# BuckBoost.net
KiCad netlist of a schematic drawn in Altium Designer
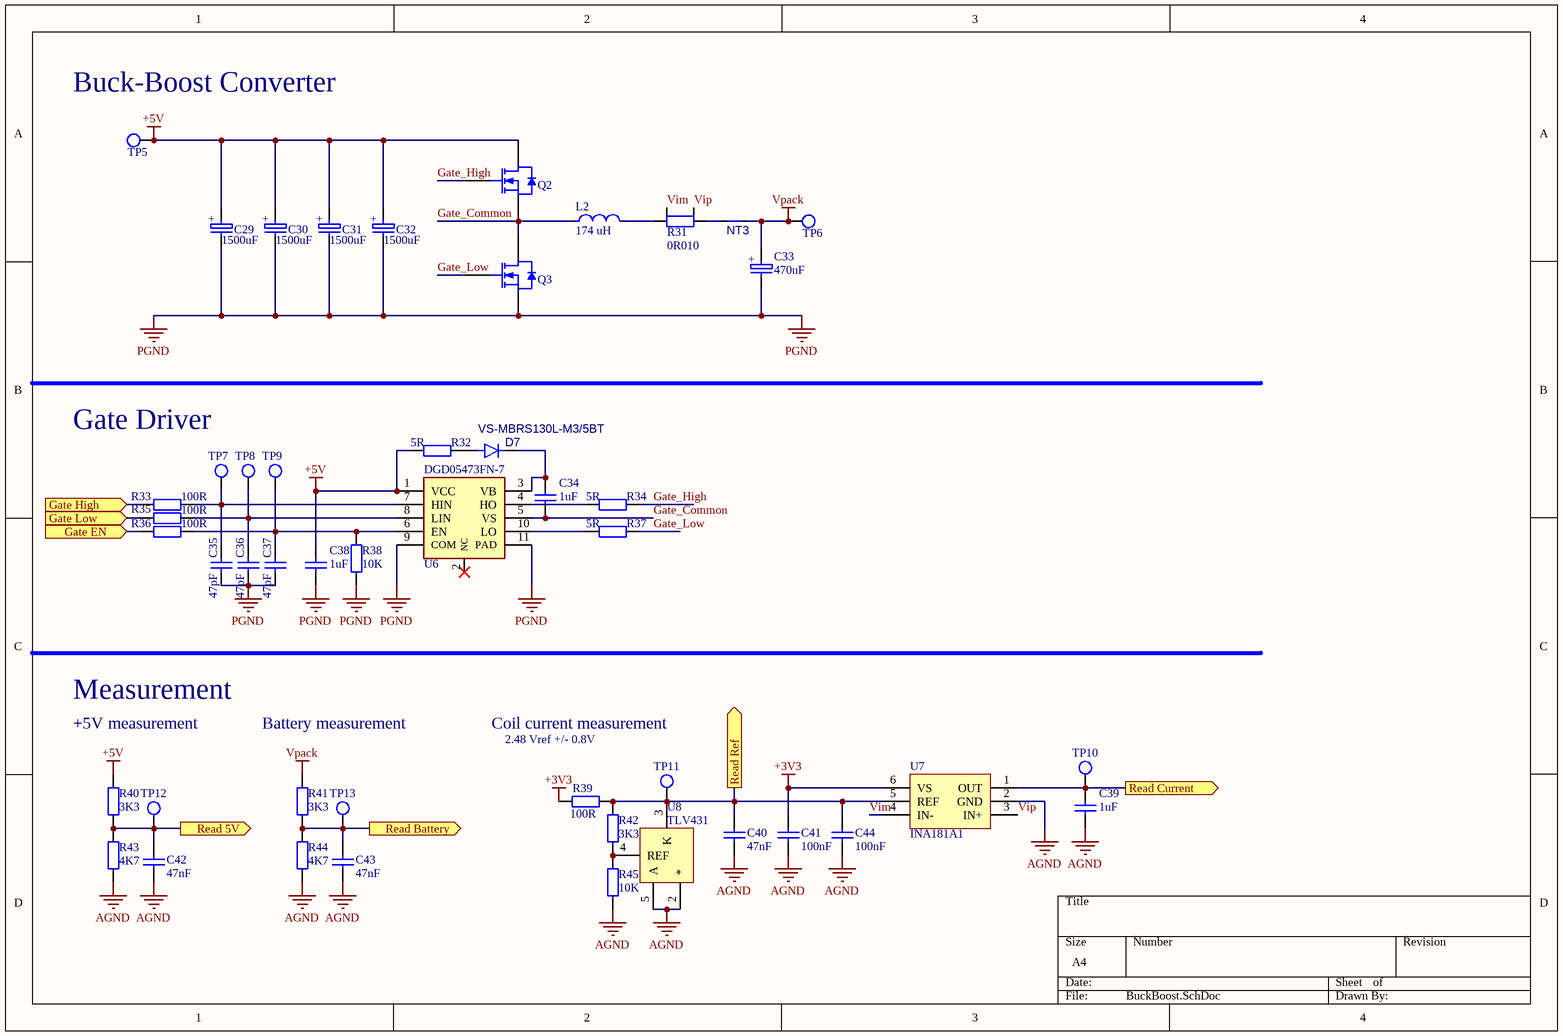
[diagram p0: BuckBoost.SchDoc]

(export (version "E")
  (design (tool "Eeschema 10.0.6"))
  (components
    (comp (ref "C29")
      (value "1500uF")
      (footprint "Aluminium Capacitor 10x12.5")
      (fields
        (field (name "MANUFACTURER") "Nichicon")
        (field (name "MANUFACTURER PART NUMBER") "RNU0J152MDN1PH")
      )
      (libsource (lib "UPS_Schlib") (part "RNU0J152MDN1PH"))
    )
    (comp (ref "C30")
      (value "1500uF")
      (footprint "Aluminium Capacitor 10x12.5")
      (fields
        (field (name "MANUFACTURER") "Nichicon")
        (field (name "MANUFACTURER PART NUMBER") "RNU0J152MDN1PH")
      )
      (libsource (lib "UPS_Schlib") (part "RNU0J152MDN1PH"))
    )
    (comp (ref "C31")
      (value "1500uF")
      (footprint "Aluminium Capacitor 10x12.5")
      (fields
        (field (name "MANUFACTURER") "Nichicon")
        (field (name "MANUFACTURER PART NUMBER") "RNU0J152MDN1PH")
      )
      (libsource (lib "UPS_Schlib") (part "RNU0J152MDN1PH"))
    )
    (comp (ref "C32")
      (value "1500uF")
      (footprint "Aluminium Capacitor 10x12.5")
      (fields
        (field (name "MANUFACTURER") "Nichicon")
        (field (name "MANUFACTURER PART NUMBER") "RNU0J152MDN1PH")
      )
      (libsource (lib "UPS_Schlib") (part "RNU0J152MDN1PH"))
    )
    (comp (ref "C33")
      (value "470uF")
      (footprint "Aluminium Capacitor 10x12.5")
      (description "Aluminum Electrolytic Capacitor, Aluminum (solid Polymer)")
      (fields
        (field (name "MANUFACTURER") "Nichicon")
        (field (name "MANUFACTURER PART NUMBER") "RR50J471MDN1KX")
      )
      (libsource (lib "UPS_Schlib") (part "RR50J471MDN1KX"))
    )
    (comp (ref "C34")
      (value "1uF")
      (footprint "CAP0603")
      (description "Capacitor")
      (libsource (lib "UPS_Schlib") (part "1uF"))
    )
    (comp (ref "C35")
      (value "47pF")
      (footprint "CAP0603")
      (fields
        (field (name "MANUFACTURER") "KEMET")
        (field (name "MANUFACTURER PART NUMBER") "C0603C470J1GACTU")
      )
      (libsource (lib "UPS_Schlib") (part "47pF"))
    )
    (comp (ref "C36")
      (value "47pF")
      (footprint "CAP0603")
      (fields
        (field (name "MANUFACTURER") "KEMET")
        (field (name "MANUFACTURER PART NUMBER") "C0603C470J1GACTU")
      )
      (libsource (lib "UPS_Schlib") (part "47pF"))
    )
    (comp (ref "C37")
      (value "47pF")
      (footprint "CAP0603")
      (fields
        (field (name "MANUFACTURER") "KEMET")
        (field (name "MANUFACTURER PART NUMBER") "C0603C470J1GACTU")
      )
      (libsource (lib "UPS_Schlib") (part "47pF"))
    )
    (comp (ref "C38")
      (value "1uF")
      (footprint "CAP0603")
      (description "Capacitor")
      (libsource (lib "UPS_Schlib") (part "1uF"))
    )
    (comp (ref "C39")
      (value "1uF")
      (footprint "CAP0603")
      (description "Capacitor")
      (libsource (lib "UPS_Schlib") (part "1uF"))
    )
    (comp (ref "C40")
      (value "47nF")
      (footprint "CAP0603")
      (description "Capacitor")
      (libsource (lib "UPS_Schlib") (part "47nF"))
    )
    (comp (ref "C41")
      (value "100nF")
      (footprint "CAP0603")
      (description "Capacitor")
      (libsource (lib "UPS_Schlib") (part "100nF"))
    )
    (comp (ref "C42")
      (value "47nF")
      (footprint "CAP0603")
      (description "Capacitor")
      (libsource (lib "UPS_Schlib") (part "47nF"))
    )
    (comp (ref "C43")
      (value "47nF")
      (footprint "CAP0603")
      (description "Capacitor")
      (libsource (lib "UPS_Schlib") (part "47nF"))
    )
    (comp (ref "C44")
      (value "100nF")
      (footprint "CAP0603")
      (description "Capacitor")
      (libsource (lib "UPS_Schlib") (part "100nF"))
    )
    (comp (ref "D7")
      (value "VS-MBRS130L-M3/5BT")
      (footprint "SMB")
      (description "Rectifier Diode, Schottky, 1 Phase, 1 Element, 30V V(RRM), Silicon")
      (fields (field (name "MANUFACTURER") "Vishay Semiconductors"))
      (libsource (lib "UPS_Schlib") (part "VS-MBRS130L-M3/5BT"))
    )
    (comp (ref "L2")
      (value "174 uH")
      (footprint "COIL_HANDMADE")
      (description "Hand made inductance")
      (fields (field (name "Comment") "Inductor"))
      (libsource (lib "UPS_Schlib") (part "Inductor"))
    )
    (comp (ref "NT3")
      (value "NetTie_1-1")
      (footprint "NETTIE_1.85MM")
      (description "NetTie 1 -> 1")
      (libsource (lib "UPS_Schlib") (part "NetTie_1-1"))
    )
    (comp (ref "Q2")
      (value "N-MOSFET")
      (footprint "SOT-669-5")
      (fields
        (field (name "MANUFACTURER") "Nexperia")
        (field (name "MANUFACTURER PART NUMBER") "PSMN1R2-25YLDX")
      )
      (libsource (lib "UPS_Schlib") (part "PSMN1R2-25YLDX"))
    )
    (comp (ref "Q3")
      (value "N-MOSFET")
      (footprint "SOT-669-5")
      (fields
        (field (name "MANUFACTURER") "Nexperia")
        (field (name "MANUFACTURER PART NUMBER") "PSMN1R2-25YLDX")
      )
      (libsource (lib "UPS_Schlib") (part "PSMN1R2-25YLDX"))
    )
    (comp (ref "R31")
      (value "0R010")
      (footprint "RES1206_KELVIN")
      (description "Resistor Current Sense Metal Foil 1206 10m Ohm 1% 1W ±50ppm/°C T/R")
      (fields
        (field (name "MANUFACTURER") "Eaton")
        (field (name "MANUFACTURER PART NUMBER") "MFSA1206R0050FCM")
      )
      (libsource (lib "UPS_Schlib") (part "0R010"))
    )
    (comp (ref "R32")
      (value "5R")
      (footprint "RES0603")
      (description "Resistor")
      (libsource (lib "UPS_Schlib") (part "5R"))
    )
    (comp (ref "R33")
      (value "100R")
      (footprint "RES0603")
      (description "Resistor")
      (libsource (lib "UPS_Schlib") (part "100R"))
    )
    (comp (ref "R34")
      (value "5R")
      (footprint "RES0603")
      (description "Resistor")
      (libsource (lib "UPS_Schlib") (part "5R"))
    )
    (comp (ref "R35")
      (value "100R")
      (footprint "RES0603")
      (description "Resistor")
      (libsource (lib "UPS_Schlib") (part "100R"))
    )
    (comp (ref "R36")
      (value "100R")
      (footprint "RES0603")
      (description "Resistor")
      (libsource (lib "UPS_Schlib") (part "100R"))
    )
    (comp (ref "R37")
      (value "5R")
      (footprint "RES0603")
      (description "Resistor")
      (libsource (lib "UPS_Schlib") (part "5R"))
    )
    (comp (ref "R38")
      (value "10K")
      (footprint "RES0603")
      (description "Resistor")
      (libsource (lib "UPS_Schlib") (part "10K"))
    )
    (comp (ref "R39")
      (value "100R")
      (footprint "RES0603")
      (description "Resistor")
      (libsource (lib "UPS_Schlib") (part "100R"))
    )
    (comp (ref "R40")
      (value "3K3")
      (footprint "RES0603")
      (fields
        (field (name "MANUFACTURER") "Yageo")
        (field (name "MANUFACTURER PART NUMBER") "RC0603FR-073K3P")
      )
      (libsource (lib "UPS_Schlib") (part "3K3"))
    )
    (comp (ref "R41")
      (value "3K3")
      (footprint "RES0603")
      (fields
        (field (name "MANUFACTURER") "Yageo")
        (field (name "MANUFACTURER PART NUMBER") "RC0603FR-073K3P")
      )
      (libsource (lib "UPS_Schlib") (part "3K3"))
    )
    (comp (ref "R42")
      (value "3K3")
      (footprint "RES0603")
      (fields
        (field (name "MANUFACTURER") "Yageo")
        (field (name "MANUFACTURER PART NUMBER") "RC0603FR-073K3P")
      )
      (libsource (lib "UPS_Schlib") (part "3K3"))
    )
    (comp (ref "R43")
      (value "4K7")
      (footprint "RES0603")
      (description "Resistor")
      (libsource (lib "UPS_Schlib") (part "4K7"))
    )
    (comp (ref "R44")
      (value "4K7")
      (footprint "RES0603")
      (description "Resistor")
      (libsource (lib "UPS_Schlib") (part "4K7"))
    )
    (comp (ref "R45")
      (value "10K")
      (footprint "RES0603")
      (description "Resistor")
      (libsource (lib "") (part "10K_1"))
    )
    (comp (ref "TP5")
      (value "Test Point")
      (footprint "TP-1.5HOLE")
      (libsource (lib "UPS_Schlib") (part "Test Point"))
    )
    (comp (ref "TP6")
      (value "Test Point")
      (footprint "TP-1.5HOLE")
      (libsource (lib "UPS_Schlib") (part "Test Point"))
    )
    (comp (ref "TP7")
      (value "Test Point")
      (footprint "TP-1.5HOLE")
      (libsource (lib "UPS_Schlib") (part "Test Point"))
    )
    (comp (ref "TP8")
      (value "Test Point")
      (footprint "TP-1.5HOLE")
      (libsource (lib "UPS_Schlib") (part "Test Point"))
    )
    (comp (ref "TP9")
      (value "Test Point")
      (footprint "TP-1.5HOLE")
      (libsource (lib "UPS_Schlib") (part "Test Point"))
    )
    (comp (ref "TP10")
      (value "Test Point")
      (footprint "TP-1.5HOLE")
      (libsource (lib "UPS_Schlib") (part "Test Point"))
    )
    (comp (ref "TP11")
      (value "Test Point")
      (footprint "TP-1.5HOLE")
      (libsource (lib "UPS_Schlib") (part "Test Point"))
    )
    (comp (ref "TP12")
      (value "Test Point")
      (footprint "TP-1.5HOLE")
      (libsource (lib "UPS_Schlib") (part "Test Point"))
    )
    (comp (ref "TP13")
      (value "Test Point")
      (footprint "TP-1.5HOLE")
      (libsource (lib "UPS_Schlib") (part "Test Point"))
    )
    (comp (ref "U6")
      (value "DGD05473FN-7")
      (footprint "V-DFN3030-10")
      (description "HIGH FREQUENCY HIGH-SIDE AND LOW-SIDE GATE DRIVER")
      (fields (field (name "MOUSER PART NUMBER") "621-DGD05473FN-7"))
      (libsource (lib "UPS_Schlib") (part "DGD05473FN-7"))
    )
    (comp (ref "U7")
      (value "INA181A1")
      (footprint "SOT23-6")
      (description "Operational Amplifier, 1 Func, 500uV Offset-Max, PDSO6")
      (fields
        (field (name "MANUFACTURER") "Texas Instruments")
        (field (name "MANUFACTURER PART NUMBER") "INA181A1IDBVR")
      )
      (libsource (lib "UPS_Schlib") (part "INA181A1"))
    )
    (comp (ref "U8")
      (value "TLV431")
      (footprint "SOT23-5")
      (description "Three Terminal Voltage Reference, 1 Output, 1.24V, Trim/Adjustable, BIPolar, PDSO5")
      (fields
        (field (name "MANUFACTURER") "Texas Instruments")
        (field (name "MANUFACTURER PART NUMBER") "TLV431CDBVR")
      )
      (libsource (lib "UPS_Schlib") (part "TLV431"))
    )
  )
  (nets
    (net (code "1") (name "+3V3") (class "Default")
      (node (ref "C41") (pin "1") (pinfunction "1_1") (pintype "passive"))
      (node (ref "R39") (pin "1") (pinfunction "1_1") (pintype "passive"))
      (node (ref "U7") (pin "6") (pinfunction "VS_6") (pintype "power_in"))
    )
    (net (code "2") (name "+5V") (class "Default")
      (node (ref "C29") (pin "2") (pinfunction "A_2") (pintype "passive"))
      (node (ref "C30") (pin "2") (pinfunction "A_2") (pintype "passive"))
      (node (ref "C31") (pin "2") (pinfunction "A_2") (pintype "passive"))
      (node (ref "C32") (pin "2") (pinfunction "A_2") (pintype "passive"))
      (node (ref "C38") (pin "2") (pinfunction "2_2") (pintype "passive"))
      (node (ref "Q2") (pin "3") (pinfunction "D_3") (pintype "passive"))
      (node (ref "R32") (pin "1") (pinfunction "1_1") (pintype "passive"))
      (node (ref "R40") (pin "2") (pinfunction "2_2") (pintype "passive"))
      (node (ref "TP5") (pin "1") (pintype "passive"))
      (node (ref "U6") (pin "1") (pinfunction "VCC_1") (pintype "passive"))
    )
    (net (code "3") (name "/Gate EN") (class "Default")
      (node (ref "R36") (pin "1") (pinfunction "1_1") (pintype "passive"))
    )
    (net (code "4") (name "/Gate High") (class "Default")
      (node (ref "R33") (pin "1") (pinfunction "1_1") (pintype "passive"))
    )
    (net (code "5") (name "/Gate Low") (class "Default")
      (node (ref "R35") (pin "1") (pinfunction "1_1") (pintype "passive"))
    )
    (net (code "6") (name "/Gate_Common") (class "Default")
      (node (ref "C34") (pin "1") (pinfunction "1_1") (pintype "passive"))
      (node (ref "L2") (pin "1") (pinfunction "1_1") (pintype "passive"))
      (node (ref "Q2") (pin "2") (pinfunction "S_2") (pintype "passive"))
      (node (ref "Q3") (pin "3") (pinfunction "D_3") (pintype "passive"))
      (node (ref "U6") (pin "5") (pinfunction "VS_5") (pintype "passive"))
    )
    (net (code "7") (name "/Gate_High") (class "Default")
      (node (ref "Q2") (pin "1") (pinfunction "G_1") (pintype "passive"))
      (node (ref "R34") (pin "2") (pinfunction "2_2") (pintype "passive"))
    )
    (net (code "8") (name "/Gate_Low") (class "Default")
      (node (ref "Q3") (pin "1") (pinfunction "G_1") (pintype "passive"))
      (node (ref "R37") (pin "2") (pinfunction "2_2") (pintype "passive"))
    )
    (net (code "9") (name "/Read 5V") (class "Default")
      (node (ref "C42") (pin "2") (pinfunction "2_2") (pintype "passive"))
      (node (ref "R40") (pin "1") (pinfunction "1_1") (pintype "passive"))
      (node (ref "R43") (pin "2") (pinfunction "2_2") (pintype "passive"))
      (node (ref "TP12") (pin "1") (pintype "passive"))
    )
    (net (code "10") (name "/Read Battery") (class "Default")
      (node (ref "C43") (pin "2") (pinfunction "2_2") (pintype "passive"))
      (node (ref "R41") (pin "1") (pinfunction "1_1") (pintype "passive"))
      (node (ref "R44") (pin "2") (pinfunction "2_2") (pintype "passive"))
      (node (ref "TP13") (pin "1") (pintype "passive"))
    )
    (net (code "11") (name "/Read Current") (class "Default")
      (node (ref "C39") (pin "2") (pinfunction "2_2") (pintype "passive"))
      (node (ref "TP10") (pin "1") (pintype "passive"))
      (node (ref "U7") (pin "1") (pinfunction "OUT_1") (pintype "passive"))
    )
    (net (code "12") (name "/Read Ref") (class "Default")
      (node (ref "C40") (pin "2") (pinfunction "2_2") (pintype "passive"))
      (node (ref "C44") (pin "1") (pinfunction "1_1") (pintype "passive"))
      (node (ref "R39") (pin "2") (pinfunction "2_2") (pintype "passive"))
      (node (ref "R42") (pin "2") (pinfunction "2_2") (pintype "passive"))
      (node (ref "TP11") (pin "1") (pintype "passive"))
      (node (ref "U7") (pin "5") (pinfunction "REF_5") (pintype "passive"))
      (node (ref "U8") (pin "3") (pinfunction "K_3") (pintype "passive"))
    )
    (net (code "13") (name "/Vim") (class "Default")
      (node (ref "R31") (pin "3") (pinfunction "3_3") (pintype "passive"))
      (node (ref "U7") (pin "4") (pinfunction "IN-_4") (pintype "passive"))
    )
    (net (code "14") (name "/Vip") (class "Default")
      (node (ref "R31") (pin "4") (pinfunction "4_4") (pintype "passive"))
      (node (ref "U7") (pin "3") (pinfunction "IN+_3") (pintype "passive"))
    )
    (net (code "15") (name "AGND") (class "Default")
      (node (ref "C39") (pin "1") (pinfunction "1_1") (pintype "passive"))
      (node (ref "C40") (pin "1") (pinfunction "1_1") (pintype "passive"))
      (node (ref "C41") (pin "2") (pinfunction "2_2") (pintype "passive"))
      (node (ref "C42") (pin "1") (pinfunction "1_1") (pintype "passive"))
      (node (ref "C43") (pin "1") (pinfunction "1_1") (pintype "passive"))
      (node (ref "C44") (pin "2") (pinfunction "2_2") (pintype "passive"))
      (node (ref "R43") (pin "1") (pinfunction "1_1") (pintype "passive"))
      (node (ref "R44") (pin "1") (pinfunction "1_1") (pintype "passive"))
      (node (ref "R45") (pin "1") (pinfunction "1_1") (pintype "passive"))
      (node (ref "U7") (pin "2") (pinfunction "GND_2") (pintype "passive"))
      (node (ref "U8") (pin "2") (pinfunction "*_2") (pintype "passive"))
      (node (ref "U8") (pin "5") (pinfunction "A_5") (pintype "passive"))
    )
    (net (code "16") (name "Net-(D7-A)") (class "Default")
      (node (ref "D7") (pin "2") (pinfunction "A_2") (pintype "passive"))
      (node (ref "R32") (pin "2") (pinfunction "2_2") (pintype "passive"))
    )
    (net (code "17") (name "Net-(D7-K)") (class "Default")
      (node (ref "C34") (pin "2") (pinfunction "2_2") (pintype "passive"))
      (node (ref "D7") (pin "1") (pinfunction "K_1") (pintype "passive"))
      (node (ref "U6") (pin "3") (pinfunction "VB_3") (pintype "passive"))
    )
    (net (code "18") (name "Net-(L2-Pad2)") (class "Default")
      (node (ref "L2") (pin "2") (pinfunction "2_2") (pintype "passive"))
      (node (ref "R31") (pin "1") (pinfunction "1_1") (pintype "passive"))
    )
    (net (code "19") (name "Net-(NT3-Pad1)") (class "Default")
      (node (ref "NT3") (pin "1") (pinfunction "1_1") (pintype "passive"))
      (node (ref "R31") (pin "2") (pinfunction "2_2") (pintype "passive"))
    )
    (net (code "20") (name "Net-(U6-EN)") (class "Default")
      (node (ref "C37") (pin "2") (pinfunction "2_2") (pintype "passive"))
      (node (ref "R36") (pin "2") (pinfunction "2_2") (pintype "passive"))
      (node (ref "R38") (pin "1") (pinfunction "1_1") (pintype "passive"))
      (node (ref "TP9") (pin "1") (pintype "passive"))
      (node (ref "U6") (pin "6") (pinfunction "EN_6") (pintype "passive"))
    )
    (net (code "21") (name "Net-(U6-HIN)") (class "Default")
      (node (ref "C35") (pin "2") (pinfunction "2_2") (pintype "passive"))
      (node (ref "R33") (pin "2") (pinfunction "2_2") (pintype "passive"))
      (node (ref "TP7") (pin "1") (pintype "passive"))
      (node (ref "U6") (pin "7") (pinfunction "HIN_7") (pintype "passive"))
    )
    (net (code "22") (name "Net-(U6-HO)") (class "Default")
      (node (ref "R34") (pin "1") (pinfunction "1_1") (pintype "passive"))
      (node (ref "U6") (pin "4") (pinfunction "HO_4") (pintype "passive"))
    )
    (net (code "23") (name "Net-(U6-LIN)") (class "Default")
      (node (ref "C36") (pin "2") (pinfunction "2_2") (pintype "passive"))
      (node (ref "R35") (pin "2") (pinfunction "2_2") (pintype "passive"))
      (node (ref "TP8") (pin "1") (pintype "passive"))
      (node (ref "U6") (pin "8") (pinfunction "LIN_8") (pintype "passive"))
    )
    (net (code "24") (name "Net-(U6-LO)") (class "Default")
      (node (ref "R37") (pin "1") (pinfunction "1_1") (pintype "passive"))
      (node (ref "U6") (pin "10") (pinfunction "LO_10") (pintype "passive"))
    )
    (net (code "25") (name "Net-(U8-REF)") (class "Default")
      (node (ref "R42") (pin "1") (pinfunction "1_1") (pintype "passive"))
      (node (ref "R45") (pin "2") (pinfunction "2_2") (pintype "passive"))
      (node (ref "U8") (pin "4") (pinfunction "REF_4") (pintype "passive"))
    )
    (net (code "26") (name "PGND") (class "Default")
      (node (ref "C29") (pin "1") (pinfunction "C_1") (pintype "passive"))
      (node (ref "C30") (pin "1") (pinfunction "C_1") (pintype "passive"))
      (node (ref "C31") (pin "1") (pinfunction "C_1") (pintype "passive"))
      (node (ref "C32") (pin "1") (pinfunction "C_1") (pintype "passive"))
      (node (ref "C33") (pin "1") (pinfunction "C_1") (pintype "passive"))
      (node (ref "C35") (pin "1") (pinfunction "1_1") (pintype "passive"))
      (node (ref "C36") (pin "1") (pinfunction "1_1") (pintype "passive"))
      (node (ref "C37") (pin "1") (pinfunction "1_1") (pintype "passive"))
      (node (ref "C38") (pin "1") (pinfunction "1_1") (pintype "passive"))
      (node (ref "Q3") (pin "2") (pinfunction "S_2") (pintype "passive"))
      (node (ref "R38") (pin "2") (pinfunction "2_2") (pintype "passive"))
      (node (ref "U6") (pin "11") (pinfunction "PAD_11") (pintype "passive"))
      (node (ref "U6") (pin "9") (pinfunction "COM_9") (pintype "passive"))
    )
    (net (code "27") (name "Vpack") (class "Default")
      (node (ref "C33") (pin "2") (pinfunction "A_2") (pintype "passive"))
      (node (ref "NT3") (pin "2") (pinfunction "2_2") (pintype "passive"))
      (node (ref "R41") (pin "2") (pinfunction "2_2") (pintype "passive"))
      (node (ref "TP6") (pin "1") (pintype "passive"))
    )
    (net (code "28") (name "unconnected-(U6-NC-Pad2)") (class "Default")
      (node (ref "U6") (pin "2") (pinfunction "NC_2") (pintype "passive+no_connect"))
    )
  )
)
